# tiny13_charlie4.net
KiCad netlist of a schematic drawn in EAGLE
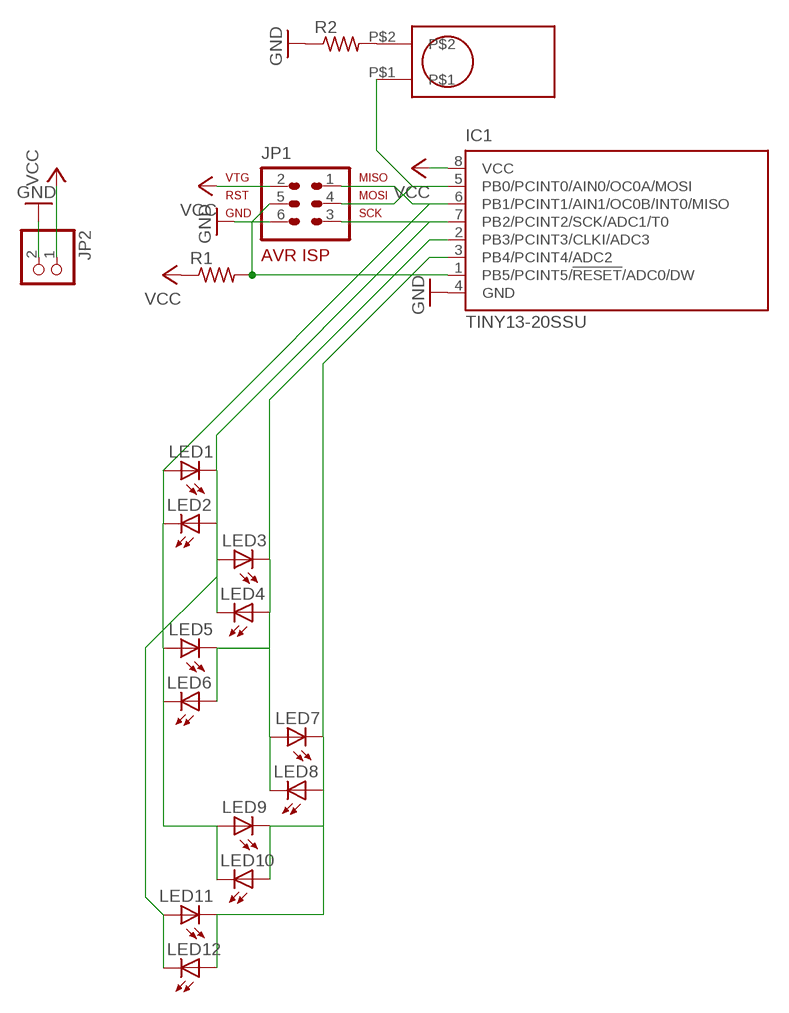
[diagram p0: schematic, sheet 1]

(export (version "E")
  (design (tool "Eeschema 10.0.6"))
  (components
    (comp (ref "IC1")
      (value "TINY13-20SSU")
      (footprint "eagle-import:8S1")
      (fields (field (name "MPN") "ATTINY13-20SSU"))
      (libsource (lib "eagle-import") (part "TINY13SSU-20"))
    )
    (comp (ref "JP1")
      (value "AVR-ISP-6R")
      (footprint "eagle-import:AVR-ISP-6R")
      (libsource (lib "eagle-import") (part "AVR-ISP-6R"))
    )
    (comp (ref "JP2")
      (value "PINHD-1X2/90")
      (footprint "eagle-import:1X02_90")
      (libsource (lib "eagle-import") (part "PINHD-1X2/90"))
    )
    (comp (ref "LED1")
      (value "LED3MM")
      (footprint "eagle-import:LED3MM")
      (libsource (lib "eagle-import") (part "LED3MM"))
    )
    (comp (ref "LED2")
      (value "LED3MM")
      (footprint "eagle-import:LED3MM")
      (libsource (lib "eagle-import") (part "LED3MM"))
    )
    (comp (ref "LED3")
      (value "LED3MM")
      (footprint "eagle-import:LED3MM")
      (libsource (lib "eagle-import") (part "LED3MM"))
    )
    (comp (ref "LED4")
      (value "LED3MM")
      (footprint "eagle-import:LED3MM")
      (libsource (lib "eagle-import") (part "LED3MM"))
    )
    (comp (ref "LED5")
      (value "LED3MM")
      (footprint "eagle-import:LED3MM")
      (libsource (lib "eagle-import") (part "LED3MM"))
    )
    (comp (ref "LED6")
      (value "LED3MM")
      (footprint "eagle-import:LED3MM")
      (libsource (lib "eagle-import") (part "LED3MM"))
    )
    (comp (ref "LED7")
      (value "LED3MM")
      (footprint "eagle-import:LED3MM")
      (libsource (lib "eagle-import") (part "LED3MM"))
    )
    (comp (ref "LED8")
      (value "LED3MM")
      (footprint "eagle-import:LED3MM")
      (libsource (lib "eagle-import") (part "LED3MM"))
    )
    (comp (ref "LED9")
      (value "LED3MM")
      (footprint "eagle-import:LED3MM")
      (libsource (lib "eagle-import") (part "LED3MM"))
    )
    (comp (ref "LED10")
      (value "LED3MM")
      (footprint "eagle-import:LED3MM")
      (libsource (lib "eagle-import") (part "LED3MM"))
    )
    (comp (ref "LED11")
      (value "LED3MM")
      (footprint "eagle-import:LED3MM")
      (libsource (lib "eagle-import") (part "LED3MM"))
    )
    (comp (ref "LED12")
      (value "LED3MM")
      (footprint "eagle-import:LED3MM")
      (libsource (lib "eagle-import") (part "LED3MM"))
    )
    (comp (ref "R1")
      (value "R-US_0207/7")
      (footprint "eagle-import:0207_7")
      (libsource (lib "eagle-import") (part "R-US_0207/7"))
    )
    (comp (ref "R2")
      (value "R-US_0207/7")
      (footprint "eagle-import:0207_7")
      (libsource (lib "eagle-import") (part "R-US_0207/7"))
    )
    (comp (ref "U$1")
      (value "TILT_SWITCH_MECHANICAL")
      (footprint "eagle-import:TILT_SWITCH_MECHANICAL")
      (libsource (lib "eagle-import") (part "TILT_SWITCH_MECHANICAL"))
    )
  )
  (nets
    (net (code "1") (name "GND") (class "Default")
      (node (ref "IC1") (pin "1") (pinfunction "PB5/PCINT5/~{RESET}/ADC0/DW_1") (pintype "bidirectional"))
      (node (ref "IC1") (pin "4") (pinfunction "GND_4") (pintype "power_in"))
      (node (ref "JP1") (pin "5") (pinfunction "5_5") (pintype "passive"))
      (node (ref "JP1") (pin "6") (pinfunction "6_6") (pintype "passive"))
      (node (ref "JP2") (pin "2") (pinfunction "2_2") (pintype "passive"))
      (node (ref "R1") (pin "2") (pinfunction "2_2") (pintype "passive"))
      (node (ref "R2") (pin "1") (pinfunction "1_1") (pintype "passive"))
    )
    (net (code "2") (name "Net-(IC1-PB0{slash}PCINT0{slash}AIN0{slash}OC0A{slash}MOSI)") (class "Default")
      (node (ref "IC1") (pin "5") (pinfunction "PB0/PCINT0/AIN0/OC0A/MOSI_5") (pintype "bidirectional"))
      (node (ref "JP1") (pin "4") (pinfunction "4_4") (pintype "passive"))
      (node (ref "U$1") (pin "P$1") (pinfunction "P$1_P$1") (pintype "bidirectional"))
    )
    (net (code "3") (name "Net-(IC1-PB1{slash}PCINT1{slash}AIN1{slash}OC0B{slash}INT0{slash}MISO)") (class "Default")
      (node (ref "IC1") (pin "6") (pinfunction "PB1/PCINT1/AIN1/OC0B/INT0/MISO_6") (pintype "bidirectional"))
      (node (ref "JP1") (pin "1") (pinfunction "1_1") (pintype "passive"))
      (node (ref "LED1") (pin "A") (pinfunction "A_A") (pintype "passive"))
      (node (ref "LED10") (pin "K") (pinfunction "C_K") (pintype "passive"))
      (node (ref "LED2") (pin "K") (pinfunction "C_K") (pintype "passive"))
      (node (ref "LED5") (pin "A") (pinfunction "A_A") (pintype "passive"))
      (node (ref "LED6") (pin "K") (pinfunction "C_K") (pintype "passive"))
      (node (ref "LED9") (pin "A") (pinfunction "A_A") (pintype "passive"))
    )
    (net (code "4") (name "Net-(IC1-PB2{slash}PCINT2{slash}SCK{slash}ADC1{slash}T0)") (class "Default")
      (node (ref "IC1") (pin "7") (pinfunction "PB2/PCINT2/SCK/ADC1/T0_7") (pintype "bidirectional"))
      (node (ref "JP1") (pin "3") (pinfunction "3_3") (pintype "passive"))
      (node (ref "LED1") (pin "K") (pinfunction "C_K") (pintype "passive"))
      (node (ref "LED11") (pin "A") (pinfunction "A_A") (pintype "passive"))
      (node (ref "LED12") (pin "K") (pinfunction "C_K") (pintype "passive"))
      (node (ref "LED2") (pin "A") (pinfunction "A_A") (pintype "passive"))
      (node (ref "LED3") (pin "A") (pinfunction "A_A") (pintype "passive"))
      (node (ref "LED4") (pin "K") (pinfunction "C_K") (pintype "passive"))
    )
    (net (code "5") (name "Net-(IC1-PB3{slash}PCINT3{slash}CLKI{slash}ADC3)") (class "Default")
      (node (ref "IC1") (pin "2") (pinfunction "PB3/PCINT3/CLKI/ADC3_2") (pintype "bidirectional"))
      (node (ref "LED3") (pin "K") (pinfunction "C_K") (pintype "passive"))
      (node (ref "LED4") (pin "A") (pinfunction "A_A") (pintype "passive"))
      (node (ref "LED5") (pin "K") (pinfunction "C_K") (pintype "passive"))
      (node (ref "LED6") (pin "A") (pinfunction "A_A") (pintype "passive"))
      (node (ref "LED7") (pin "A") (pinfunction "A_A") (pintype "passive"))
      (node (ref "LED8") (pin "K") (pinfunction "C_K") (pintype "passive"))
    )
    (net (code "6") (name "Net-(IC1-PB4{slash}PCINT4{slash}ADC2)") (class "Default")
      (node (ref "IC1") (pin "3") (pinfunction "PB4/PCINT4/ADC2_3") (pintype "bidirectional"))
      (node (ref "LED10") (pin "A") (pinfunction "A_A") (pintype "passive"))
      (node (ref "LED11") (pin "K") (pinfunction "C_K") (pintype "passive"))
      (node (ref "LED12") (pin "A") (pinfunction "A_A") (pintype "passive"))
      (node (ref "LED7") (pin "K") (pinfunction "C_K") (pintype "passive"))
      (node (ref "LED8") (pin "A") (pinfunction "A_A") (pintype "passive"))
      (node (ref "LED9") (pin "K") (pinfunction "C_K") (pintype "passive"))
    )
    (net (code "7") (name "Net-(R2-Pad2)") (class "Default")
      (node (ref "R2") (pin "2") (pinfunction "2_2") (pintype "passive"))
      (node (ref "U$1") (pin "P$2") (pinfunction "P$2_P$2") (pintype "bidirectional"))
    )
    (net (code "8") (name "VCC") (class "Default")
      (node (ref "IC1") (pin "8") (pinfunction "VCC_8") (pintype "power_in"))
      (node (ref "JP1") (pin "2") (pinfunction "2_2") (pintype "passive"))
      (node (ref "JP2") (pin "1") (pinfunction "1_1") (pintype "passive"))
      (node (ref "R1") (pin "1") (pinfunction "1_1") (pintype "passive"))
    )
  )
)
